# daGloane.net
KiCad netlist of a schematic drawn in EAGLE
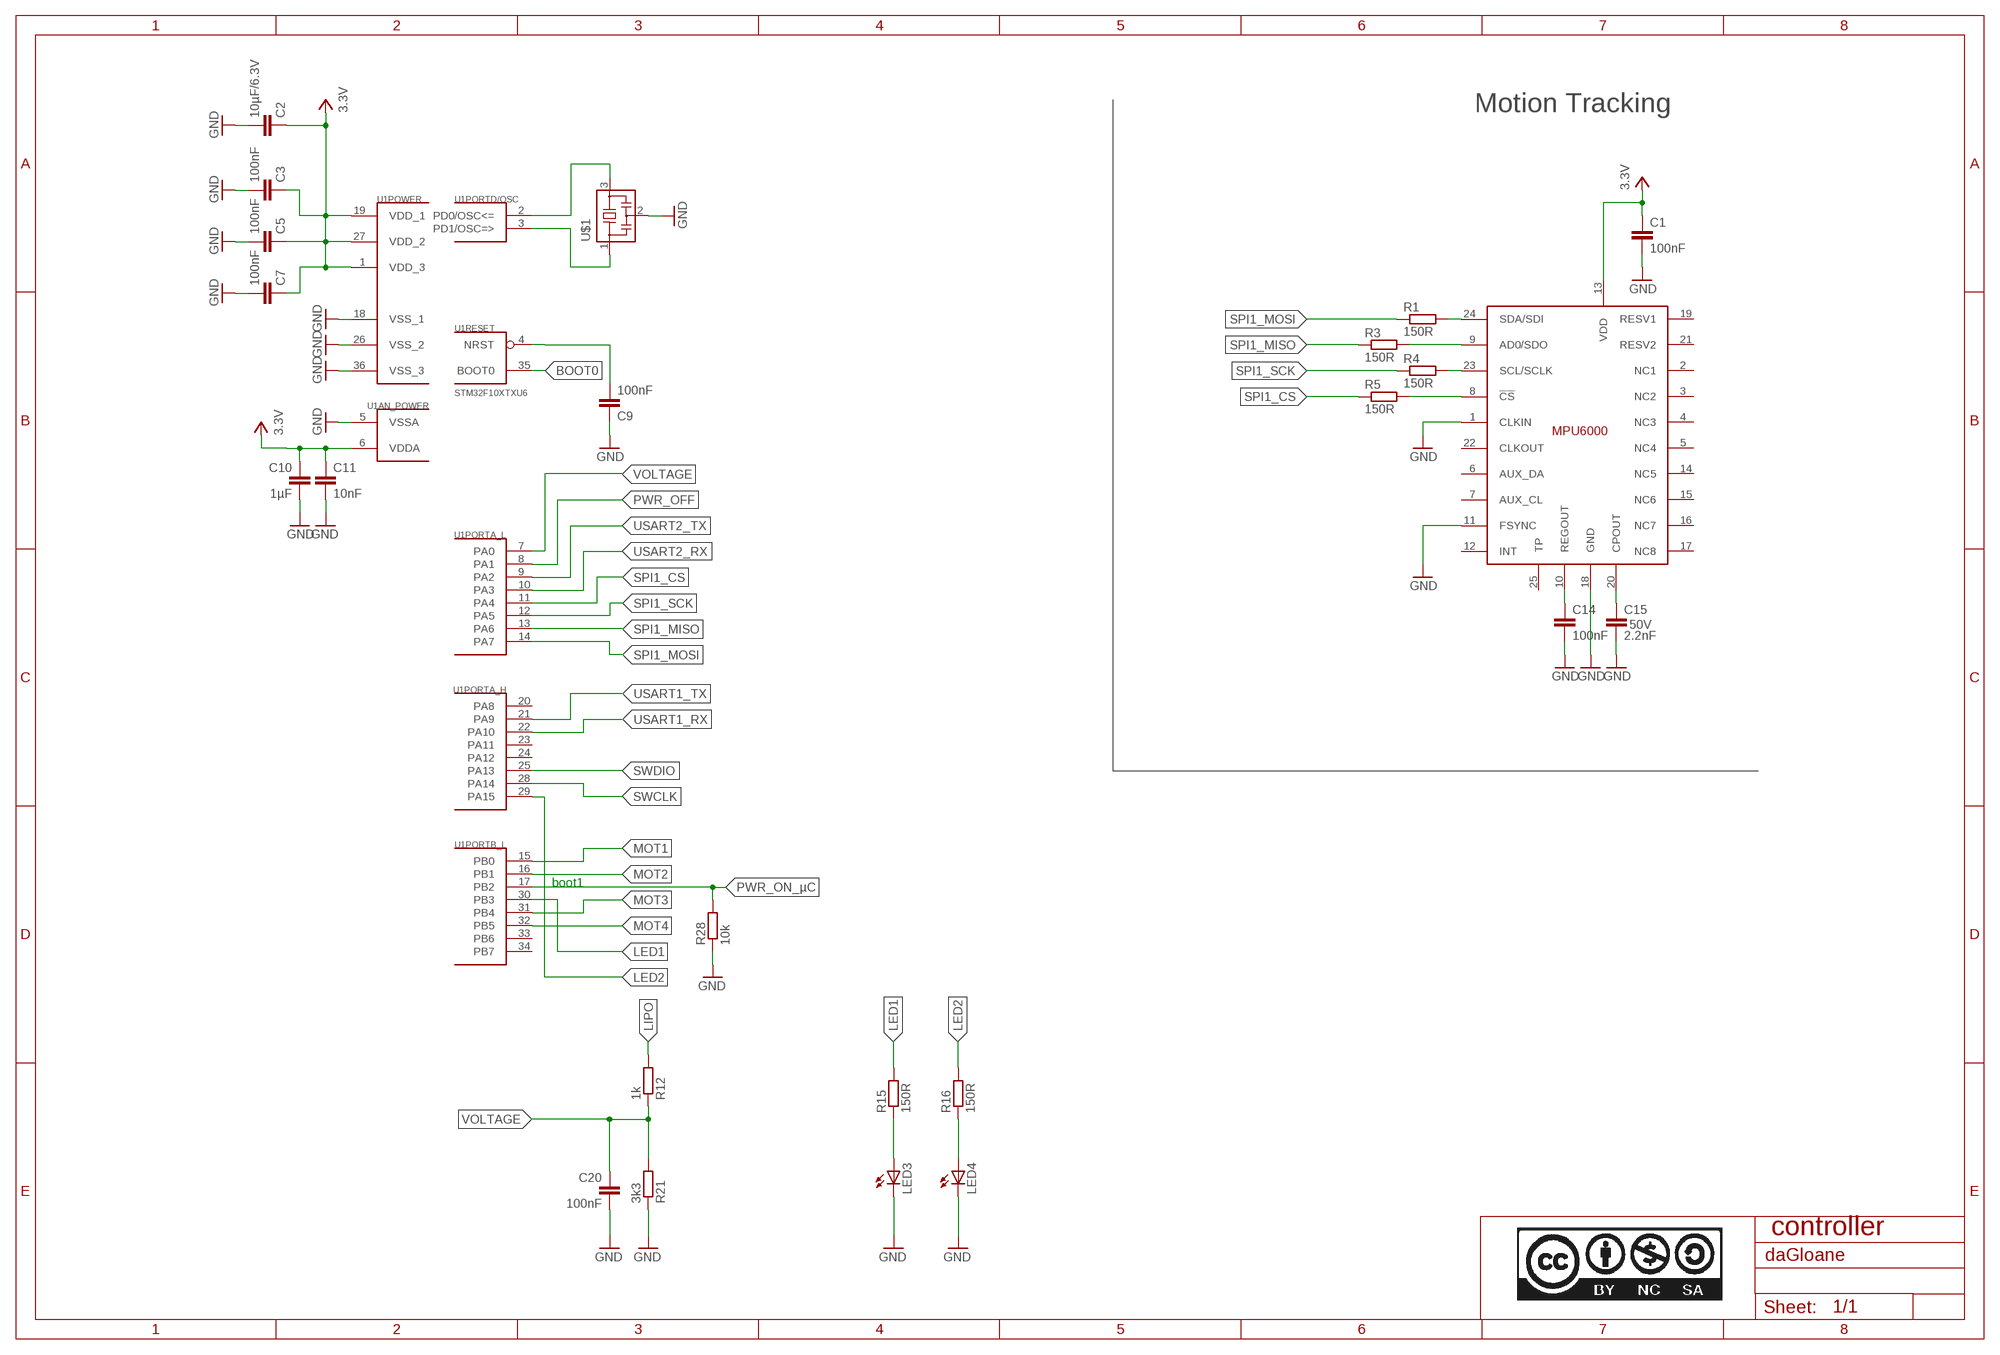
[diagram p0: schematic, sheet 1, part 1 of 3]
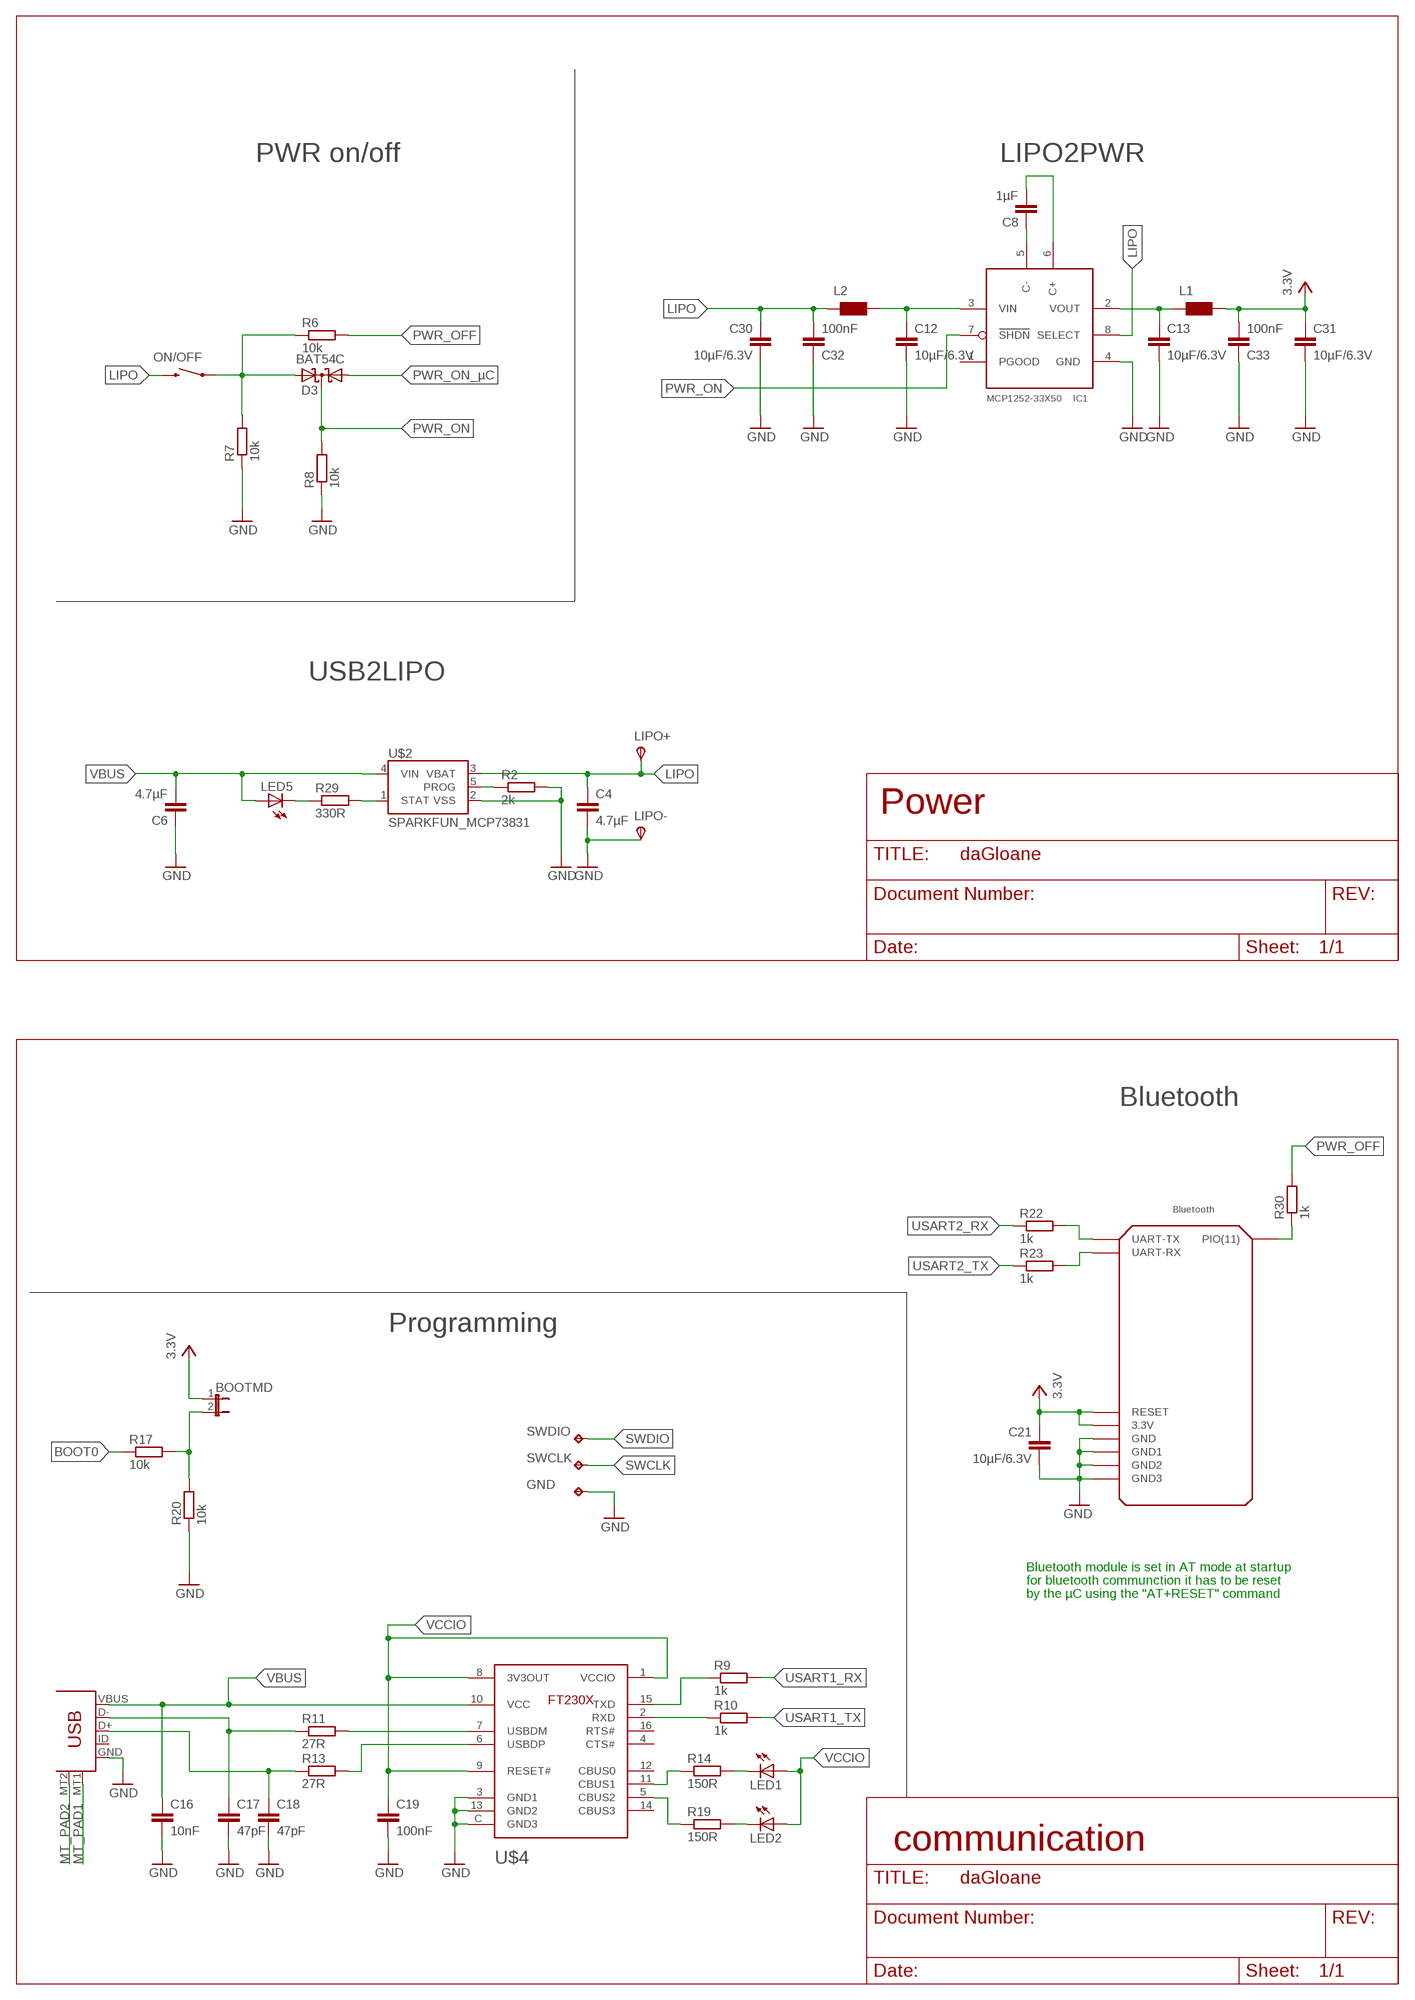
[diagram p1: schematic, sheet 1, part 2 of 3]
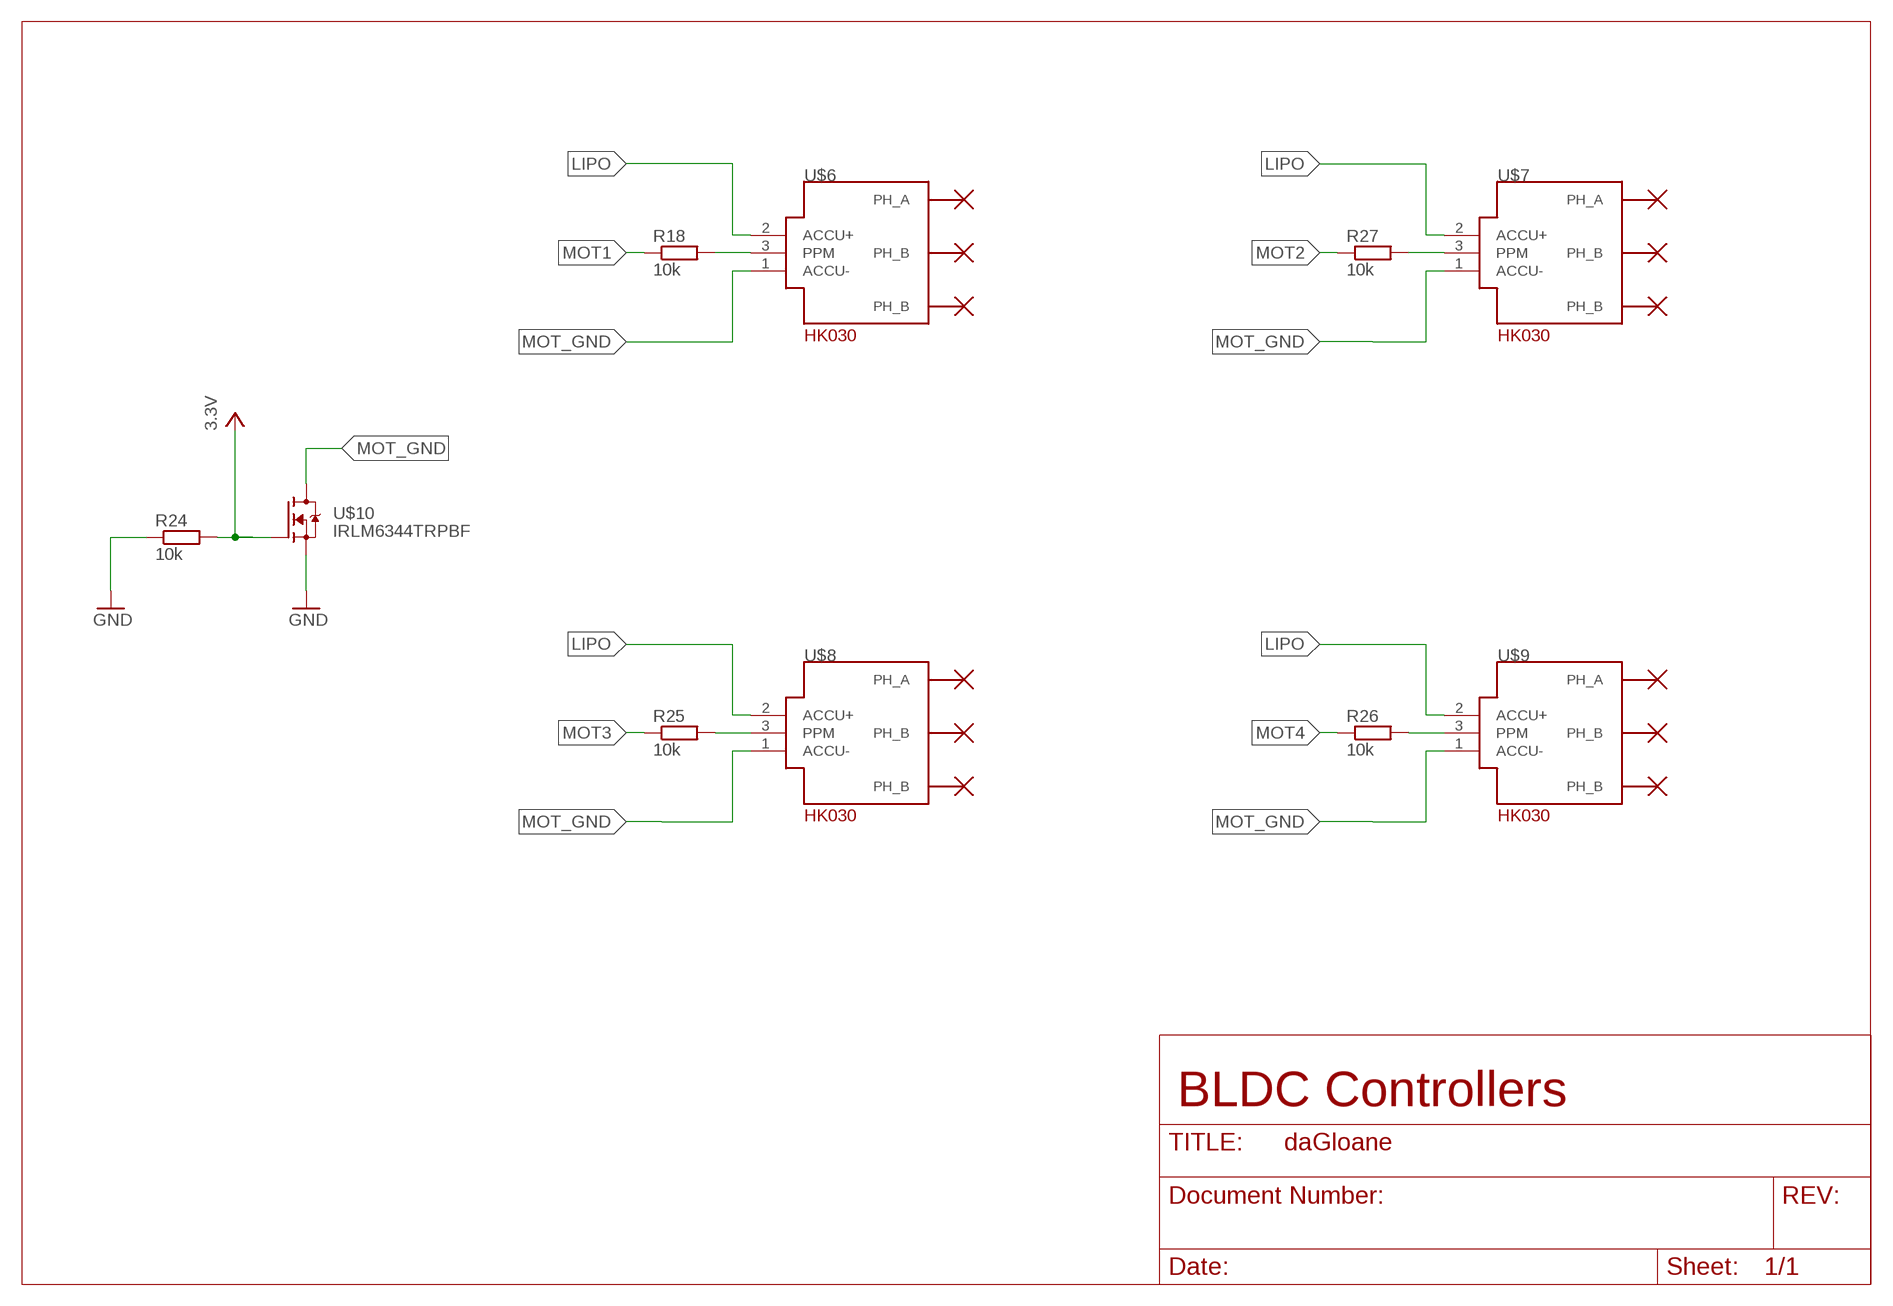
[diagram p2: schematic, sheet 1, part 3 of 3]

(export (version "E")
  (design (tool "Eeschema 10.0.6"))
  (components
    (comp (ref "BOOTMD")
      (value "JUMPER-2")
      (footprint "eagle-import:1X02_50MIL")
      (libsource (lib "eagle-import") (part "JUMPER-2"))
    )
    (comp (ref "C1")
      (value "100nF")
      (footprint "eagle-import:C0603")
      (libsource (lib "eagle-import") (part "C-EUC0603"))
    )
    (comp (ref "C2")
      (value "10µF/6.3V")
      (footprint "eagle-import:C0805")
      (libsource (lib "eagle-import") (part "C-EUC0805"))
    )
    (comp (ref "C3")
      (value "100nF")
      (footprint "eagle-import:C0603")
      (libsource (lib "eagle-import") (part "C-EUC0603"))
    )
    (comp (ref "C4")
      (value "4.7µF")
      (footprint "eagle-import:C0603")
      (libsource (lib "eagle-import") (part "C-EUC0603"))
    )
    (comp (ref "C5")
      (value "100nF")
      (footprint "eagle-import:C0603")
      (libsource (lib "eagle-import") (part "C-EUC0603"))
    )
    (comp (ref "C6")
      (value "4.7µF")
      (footprint "eagle-import:C0603")
      (libsource (lib "eagle-import") (part "C-EUC0603"))
    )
    (comp (ref "C7")
      (value "100nF")
      (footprint "eagle-import:C0603")
      (libsource (lib "eagle-import") (part "C-EUC0603"))
    )
    (comp (ref "C8")
      (value "1µF")
      (footprint "eagle-import:C0603")
      (libsource (lib "eagle-import") (part "C-EUC0603"))
    )
    (comp (ref "C9")
      (value "100nF")
      (footprint "eagle-import:C0603")
      (libsource (lib "eagle-import") (part "C-EUC0603"))
    )
    (comp (ref "C10")
      (value "1µF")
      (footprint "eagle-import:C0603")
      (libsource (lib "eagle-import") (part "C-EUC0603"))
    )
    (comp (ref "C11")
      (value "10nF")
      (footprint "eagle-import:C0603")
      (libsource (lib "eagle-import") (part "C-EUC0603"))
    )
    (comp (ref "C12")
      (value "10µF/6.3V")
      (footprint "eagle-import:C0805")
      (libsource (lib "eagle-import") (part "C-EUC0805"))
    )
    (comp (ref "C13")
      (value "10µF/6.3V")
      (footprint "eagle-import:C0805")
      (libsource (lib "eagle-import") (part "C-EUC0805"))
    )
    (comp (ref "C14")
      (value "100nF")
      (footprint "eagle-import:C0603")
      (libsource (lib "eagle-import") (part "C-EUC0603"))
    )
    (comp (ref "C15")
      (value "2.2nF")
      (footprint "eagle-import:C0603")
      (fields (field (name "VOLTAGE") "50V"))
      (libsource (lib "eagle-import") (part "C-EUC0603"))
    )
    (comp (ref "C16")
      (value "10nF")
      (footprint "eagle-import:C0603")
      (libsource (lib "eagle-import") (part "C-EUC0603"))
    )
    (comp (ref "C17")
      (value "47pF")
      (footprint "eagle-import:C0603")
      (libsource (lib "eagle-import") (part "C-EUC0603"))
    )
    (comp (ref "C18")
      (value "47pF")
      (footprint "eagle-import:C0603")
      (libsource (lib "eagle-import") (part "C-EUC0603"))
    )
    (comp (ref "C19")
      (value "100nF")
      (footprint "eagle-import:C0603")
      (libsource (lib "eagle-import") (part "C-EUC0603"))
    )
    (comp (ref "C20")
      (value "100nF")
      (footprint "eagle-import:C0603")
      (libsource (lib "eagle-import") (part "C-EUC0603"))
    )
    (comp (ref "C21")
      (value "10µF/6.3V")
      (footprint "eagle-import:C0805")
      (libsource (lib "eagle-import") (part "C-EUC0805"))
    )
    (comp (ref "C30")
      (value "10µF/6.3V")
      (footprint "eagle-import:C0805")
      (libsource (lib "eagle-import") (part "C-EUC0805"))
    )
    (comp (ref "C31")
      (value "10µF/6.3V")
      (footprint "eagle-import:C0805")
      (libsource (lib "eagle-import") (part "C-EUC0805"))
    )
    (comp (ref "C32")
      (value "100nF")
      (footprint "eagle-import:C0603")
      (libsource (lib "eagle-import") (part "C-EUC0603"))
    )
    (comp (ref "C33")
      (value "100nF")
      (footprint "eagle-import:C0603")
      (libsource (lib "eagle-import") (part "C-EUC0603"))
    )
    (comp (ref "D3")
      (value "BAT54C")
      (footprint "eagle-import:SOT23")
      (libsource (lib "eagle-import") (part "BAT54C"))
    )
    (comp (ref "GND")
      (value "TESTPAD_TPB1,27")
      (footprint "eagle-import:TESTPAD_B1,27")
      (libsource (lib "eagle-import") (part "TESTPAD_TPB1,27"))
    )
    (comp (ref "IC1")
      (value "MCP1252-33X50")
      (footprint "eagle-import:MSOP8")
      (libsource (lib "eagle-import") (part "MCP1252-33X50"))
    )
    (comp (ref "L1")
      (value "WUERTH-ELEKTRONIK_WE-KI_0805_B")
      (footprint "eagle-import:WUERTH-ELEKTRONIK_WE-KI_0805_B")
      (libsource (lib "eagle-import") (part "WUERTH-ELEKTRONIK_WE-KI_0805_B"))
    )
    (comp (ref "L2")
      (value "WUERTH-ELEKTRONIK_WE-KI_0805_B")
      (footprint "eagle-import:WUERTH-ELEKTRONIK_WE-KI_0805_B")
      (libsource (lib "eagle-import") (part "WUERTH-ELEKTRONIK_WE-KI_0805_B"))
    )
    (comp (ref "LED1")
      (value "LEDCHIPLED_0603")
      (footprint "eagle-import:CHIPLED_0603")
      (libsource (lib "eagle-import") (part "LEDCHIPLED_0603"))
    )
    (comp (ref "LED2")
      (value "LEDCHIPLED_0603")
      (footprint "eagle-import:CHIPLED_0603")
      (libsource (lib "eagle-import") (part "LEDCHIPLED_0603"))
    )
    (comp (ref "LED3")
      (value "LEDCHIPLED_0603")
      (footprint "eagle-import:CHIPLED_0603")
      (libsource (lib "eagle-import") (part "LEDCHIPLED_0603"))
    )
    (comp (ref "LED4")
      (value "LEDCHIPLED_0603")
      (footprint "eagle-import:CHIPLED_0603")
      (libsource (lib "eagle-import") (part "LEDCHIPLED_0603"))
    )
    (comp (ref "LED5")
      (value "LEDCHIPLED_0603")
      (footprint "eagle-import:CHIPLED_0603")
      (libsource (lib "eagle-import") (part "LEDCHIPLED_0603"))
    )
    (comp (ref "LIPO+")
      (value "TPSPAD1-13")
      (footprint "eagle-import:P1-13")
      (libsource (lib "eagle-import") (part "TPSPAD1-13"))
    )
    (comp (ref "LIPO-")
      (value "TPSPAD1-13")
      (footprint "eagle-import:P1-13")
      (libsource (lib "eagle-import") (part "TPSPAD1-13"))
    )
    (comp (ref "ON/OFF")
      (value "SWITCH-MOMENTARY-2SMD")
      (footprint "eagle-import:TACTILE_SWITCH_SMD")
      (libsource (lib "eagle-import") (part "SWITCH-MOMENTARY-2SMD"))
    )
    (comp (ref "R1")
      (value "150R")
      (footprint "eagle-import:R0603")
      (libsource (lib "eagle-import") (part "R-EU_R0603"))
    )
    (comp (ref "R2")
      (value "2k")
      (footprint "eagle-import:R0603")
      (libsource (lib "eagle-import") (part "R-EU_R0603"))
    )
    (comp (ref "R3")
      (value "150R")
      (footprint "eagle-import:R0603")
      (libsource (lib "eagle-import") (part "R-EU_R0603"))
    )
    (comp (ref "R4")
      (value "150R")
      (footprint "eagle-import:R0603")
      (libsource (lib "eagle-import") (part "R-EU_R0603"))
    )
    (comp (ref "R5")
      (value "150R")
      (footprint "eagle-import:R0603")
      (libsource (lib "eagle-import") (part "R-EU_R0603"))
    )
    (comp (ref "R6")
      (value "10k")
      (footprint "eagle-import:R0603")
      (libsource (lib "eagle-import") (part "R-EU_R0603"))
    )
    (comp (ref "R7")
      (value "10k")
      (footprint "eagle-import:R0603")
      (libsource (lib "eagle-import") (part "R-EU_R0603"))
    )
    (comp (ref "R8")
      (value "10k")
      (footprint "eagle-import:R0603")
      (libsource (lib "eagle-import") (part "R-EU_R0603"))
    )
    (comp (ref "R9")
      (value "1k")
      (footprint "eagle-import:R0603")
      (libsource (lib "eagle-import") (part "R-EU_R0603"))
    )
    (comp (ref "R10")
      (value "1k")
      (footprint "eagle-import:R0603")
      (libsource (lib "eagle-import") (part "R-EU_R0603"))
    )
    (comp (ref "R11")
      (value "27R")
      (footprint "eagle-import:R0603")
      (libsource (lib "eagle-import") (part "R-EU_R0603"))
    )
    (comp (ref "R12")
      (value "1k")
      (footprint "eagle-import:R0603")
      (libsource (lib "eagle-import") (part "R-EU_R0603"))
    )
    (comp (ref "R13")
      (value "27R")
      (footprint "eagle-import:R0603")
      (libsource (lib "eagle-import") (part "R-EU_R0603"))
    )
    (comp (ref "R14")
      (value "150R")
      (footprint "eagle-import:R0603")
      (libsource (lib "eagle-import") (part "R-EU_R0603"))
    )
    (comp (ref "R15")
      (value "150R")
      (footprint "eagle-import:R0603")
      (libsource (lib "eagle-import") (part "R-EU_R0603"))
    )
    (comp (ref "R16")
      (value "150R")
      (footprint "eagle-import:R0603")
      (libsource (lib "eagle-import") (part "R-EU_R0603"))
    )
    (comp (ref "R17")
      (value "10k")
      (footprint "eagle-import:R0603")
      (libsource (lib "eagle-import") (part "R-EU_R0603"))
    )
    (comp (ref "R18")
      (value "10k")
      (footprint "eagle-import:R0603")
      (libsource (lib "eagle-import") (part "R-EU_R0603"))
    )
    (comp (ref "R19")
      (value "150R")
      (footprint "eagle-import:R0603")
      (libsource (lib "eagle-import") (part "R-EU_R0603"))
    )
    (comp (ref "R20")
      (value "10k")
      (footprint "eagle-import:R0603")
      (libsource (lib "eagle-import") (part "R-EU_R0603"))
    )
    (comp (ref "R21")
      (value "3k3")
      (footprint "eagle-import:R0603")
      (libsource (lib "eagle-import") (part "R-EU_R0603"))
    )
    (comp (ref "R22")
      (value "1k")
      (footprint "eagle-import:R0603")
      (libsource (lib "eagle-import") (part "R-EU_R0603"))
    )
    (comp (ref "R23")
      (value "1k")
      (footprint "eagle-import:R0603")
      (libsource (lib "eagle-import") (part "R-EU_R0603"))
    )
    (comp (ref "R24")
      (value "10k")
      (footprint "eagle-import:R0603")
      (libsource (lib "eagle-import") (part "R-EU_R0603"))
    )
    (comp (ref "R25")
      (value "10k")
      (footprint "eagle-import:R0603")
      (libsource (lib "eagle-import") (part "R-EU_R0603"))
    )
    (comp (ref "R26")
      (value "10k")
      (footprint "eagle-import:R0603")
      (libsource (lib "eagle-import") (part "R-EU_R0603"))
    )
    (comp (ref "R27")
      (value "10k")
      (footprint "eagle-import:R0603")
      (libsource (lib "eagle-import") (part "R-EU_R0603"))
    )
    (comp (ref "R28")
      (value "10k")
      (footprint "eagle-import:R0603")
      (libsource (lib "eagle-import") (part "R-EU_R0603"))
    )
    (comp (ref "R29")
      (value "330R")
      (footprint "eagle-import:R0603")
      (libsource (lib "eagle-import") (part "R-EU_R0603"))
    )
    (comp (ref "R30")
      (value "1k")
      (footprint "eagle-import:R0603")
      (libsource (lib "eagle-import") (part "R-EU_R0603"))
    )
    (comp (ref "SWCLK")
      (value "TESTPAD_TPB1,27")
      (footprint "eagle-import:TESTPAD_B1,27")
      (libsource (lib "eagle-import") (part "TESTPAD_TPB1,27"))
    )
    (comp (ref "SWDIO")
      (value "TESTPAD_TPB1,27")
      (footprint "eagle-import:TESTPAD_B1,27")
      (libsource (lib "eagle-import") (part "TESTPAD_TPB1,27"))
    )
    (comp (ref "U$1")
      (value "MURATA-FILTER_CSTCE__G")
      (footprint "eagle-import:MURATA-FILTER_CSTCE__G")
      (libsource (lib "eagle-import") (part "MURATA-FILTER_CSTCE__G"))
    )
    (comp (ref "U$2")
      (value "SPARKFUN_MCP73831")
      (footprint "eagle-import:SPARKFUN_SOT23-5")
      (libsource (lib "eagle-import") (part "SPARKFUN_MCP73831"))
    )
    (comp (ref "U$3")
      (value "MPU6000")
      (footprint "eagle-import:MPU6000")
      (libsource (lib "eagle-import") (part "MPU6000"))
    )
    (comp (ref "U$4")
      (value "SERIAL_FT230XQ")
      (footprint "eagle-import:SERIAL_QFN4X4-16")
      (libsource (lib "eagle-import") (part "SERIAL_FT230XQ"))
    )
    (comp (ref "U$5")
      (value "BLUETOOTH_REDUCED")
      (footprint "eagle-import:BLUETOOTH_REDUCED")
      (libsource (lib "eagle-import") (part "BLUETOOTH_REDUCED"))
    )
    (comp (ref "U$6")
      (value "3A_BLDC_CONTROLLER")
      (footprint "eagle-import:3A_BLDC_CONTROLLER")
      (libsource (lib "eagle-import") (part "3A_BLDC_CONTROLLER"))
    )
    (comp (ref "U$7")
      (value "3A_BLDC_CONTROLLER")
      (footprint "eagle-import:3A_BLDC_CONTROLLER")
      (libsource (lib "eagle-import") (part "3A_BLDC_CONTROLLER"))
    )
    (comp (ref "U$8")
      (value "3A_BLDC_CONTROLLER")
      (footprint "eagle-import:3A_BLDC_CONTROLLER")
      (libsource (lib "eagle-import") (part "3A_BLDC_CONTROLLER"))
    )
    (comp (ref "U$9")
      (value "3A_BLDC_CONTROLLER")
      (footprint "eagle-import:3A_BLDC_CONTROLLER")
      (libsource (lib "eagle-import") (part "3A_BLDC_CONTROLLER"))
    )
    (comp (ref "U$10")
      (value "IRLM6344TRPBF")
      (footprint "eagle-import:MICRO3(SOT-23)")
      (libsource (lib "eagle-import") (part "IRLM6344TRPBF"))
    )
    (comp (ref "U1")
      (value "STM32F10XTXU6")
      (footprint "eagle-import:VFQFPN36")
      (libsource (lib "eagle-import") (part "STM32F10XTXU6"))
    )
    (comp (ref "X2")
      (value "USB_MICROB_PLUG_MT")
      (footprint "eagle-import:SPARKFUN-CONNECTORS_USB-MICROB")
      (libsource (lib "eagle-import") (part "USB_MICROB_PLUG_MT"))
    )
  )
  (nets
    (net (code "3") (name "/MT_PAD1") (class "Default")
      (node (ref "X2") (pin "MT1") (pinfunction "MTN1_MT1") (pintype "no_connect"))
    )
    (net (code "4") (name "/MT_PAD2") (class "Default")
      (node (ref "X2") (pin "MT2") (pinfunction "MTN2_MT2") (pintype "no_connect"))
    )
    (net (code "5") (name "3.3V") (class "Default")
      (node (ref "BOOTMD") (pin "1") (pinfunction "1_1") (pintype "passive"))
      (node (ref "C1") (pin "1") (pinfunction "1_1") (pintype "passive"))
      (node (ref "C10") (pin "1") (pinfunction "1_1") (pintype "passive"))
      (node (ref "C11") (pin "1") (pinfunction "1_1") (pintype "passive"))
      (node (ref "C2") (pin "1") (pinfunction "1_1") (pintype "passive"))
      (node (ref "C21") (pin "1") (pinfunction "1_1") (pintype "passive"))
      (node (ref "C3") (pin "1") (pinfunction "1_1") (pintype "passive"))
      (node (ref "C31") (pin "1") (pinfunction "1_1") (pintype "passive"))
      (node (ref "C33") (pin "2") (pinfunction "2_2") (pintype "passive"))
      (node (ref "C5") (pin "1") (pinfunction "1_1") (pintype "passive"))
      (node (ref "C7") (pin "1") (pinfunction "1_1") (pintype "passive"))
      (node (ref "L1") (pin "1") (pinfunction "2_1") (pintype "passive"))
      (node (ref "R24") (pin "2") (pinfunction "2_2") (pintype "passive"))
      (node (ref "U$10") (pin "1") (pinfunction "G_1") (pintype "passive"))
      (node (ref "U$3") (pin "13") (pinfunction "VDD_13") (pintype "power_in"))
      (node (ref "U$5") (pin "P$11") (pinfunction "RESET_P$11") (pintype "input"))
      (node (ref "U$5") (pin "P$12") (pinfunction "3.3V_P$12") (pintype "power_in"))
      (node (ref "U1") (pin "1") (pinfunction "VDD_3_1") (pintype "power_in"))
      (node (ref "U1") (pin "19") (pinfunction "VDD_1_19") (pintype "power_in"))
      (node (ref "U1") (pin "27") (pinfunction "VDD_2_27") (pintype "power_in"))
      (node (ref "U1") (pin "6") (pinfunction "VDDA_6") (pintype "power_in"))
    )
    (net (code "6") (name "BOOT0") (class "Default")
      (node (ref "R17") (pin "1") (pinfunction "1_1") (pintype "passive"))
      (node (ref "U1") (pin "35") (pinfunction "BOOT0_35") (pintype "input"))
    )
    (net (code "7") (name "GND") (class "Default")
      (node (ref "C1") (pin "2") (pinfunction "2_2") (pintype "passive"))
      (node (ref "C10") (pin "2") (pinfunction "2_2") (pintype "passive"))
      (node (ref "C11") (pin "2") (pinfunction "2_2") (pintype "passive"))
      (node (ref "C12") (pin "2") (pinfunction "2_2") (pintype "passive"))
      (node (ref "C13") (pin "2") (pinfunction "2_2") (pintype "passive"))
      (node (ref "C14") (pin "2") (pinfunction "2_2") (pintype "passive"))
      (node (ref "C15") (pin "2") (pinfunction "2_2") (pintype "passive"))
      (node (ref "C16") (pin "2") (pinfunction "2_2") (pintype "passive"))
      (node (ref "C17") (pin "2") (pinfunction "2_2") (pintype "passive"))
      (node (ref "C18") (pin "2") (pinfunction "2_2") (pintype "passive"))
      (node (ref "C19") (pin "2") (pinfunction "2_2") (pintype "passive"))
      (node (ref "C2") (pin "2") (pinfunction "2_2") (pintype "passive"))
      (node (ref "C20") (pin "2") (pinfunction "2_2") (pintype "passive"))
      (node (ref "C21") (pin "2") (pinfunction "2_2") (pintype "passive"))
      (node (ref "C3") (pin "2") (pinfunction "2_2") (pintype "passive"))
      (node (ref "C30") (pin "2") (pinfunction "2_2") (pintype "passive"))
      (node (ref "C31") (pin "2") (pinfunction "2_2") (pintype "passive"))
      (node (ref "C32") (pin "1") (pinfunction "1_1") (pintype "passive"))
      (node (ref "C33") (pin "1") (pinfunction "1_1") (pintype "passive"))
      (node (ref "C4") (pin "2") (pinfunction "2_2") (pintype "passive"))
      (node (ref "C5") (pin "2") (pinfunction "2_2") (pintype "passive"))
      (node (ref "C6") (pin "1") (pinfunction "1_1") (pintype "passive"))
      (node (ref "C7") (pin "2") (pinfunction "2_2") (pintype "passive"))
      (node (ref "C9") (pin "1") (pinfunction "1_1") (pintype "passive"))
      (node (ref "GND") (pin "PP") (pinfunction "TP_PP") (pintype "input"))
      (node (ref "IC1") (pin "4") (pinfunction "GND_4") (pintype "power_in"))
      (node (ref "LED3") (pin "C") (pinfunction "C_C") (pintype "passive"))
      (node (ref "LED4") (pin "C") (pinfunction "C_C") (pintype "passive"))
      (node (ref "LIPO-") (pin "TP") (pinfunction "PP_TP") (pintype "input"))
      (node (ref "R2") (pin "2") (pinfunction "2_2") (pintype "passive"))
      (node (ref "R20") (pin "1") (pinfunction "1_1") (pintype "passive"))
      (node (ref "R21") (pin "1") (pinfunction "1_1") (pintype "passive"))
      (node (ref "R24") (pin "1") (pinfunction "1_1") (pintype "passive"))
      (node (ref "R28") (pin "1") (pinfunction "1_1") (pintype "passive"))
      (node (ref "R7") (pin "1") (pinfunction "1_1") (pintype "passive"))
      (node (ref "R8") (pin "1") (pinfunction "1_1") (pintype "passive"))
      (node (ref "U$1") (pin "2") (pinfunction "2_2") (pintype "passive"))
      (node (ref "U$10") (pin "2") (pinfunction "S_2") (pintype "passive"))
      (node (ref "U$2") (pin "2") (pinfunction "VSS_2") (pintype "power_in"))
      (node (ref "U$3") (pin "1") (pinfunction "CLKIN_1") (pintype "input"))
      (node (ref "U$3") (pin "11") (pinfunction "FSYNC_11") (pintype "input"))
      (node (ref "U$3") (pin "18") (pinfunction "GND_18") (pintype "power_in"))
      (node (ref "U$4") (pin "13") (pinfunction "GND2_13") (pintype "power_in"))
      (node (ref "U$4") (pin "3") (pinfunction "GND1_3") (pintype "power_in"))
      (node (ref "U$4") (pin "C") (pinfunction "GND3_C") (pintype "power_in"))
      (node (ref "U$5") (pin "P$13") (pinfunction "GND_P$13") (pintype "power_in"))
      (node (ref "U$5") (pin "P$14") (pinfunction "GND1_P$14") (pintype "power_in"))
      (node (ref "U$5") (pin "P$21") (pinfunction "GND2_P$21") (pintype "power_in"))
      (node (ref "U$5") (pin "P$22") (pinfunction "GND3_P$22") (pintype "power_in"))
      (node (ref "U1") (pin "18") (pinfunction "VSS_1_18") (pintype "power_in"))
      (node (ref "U1") (pin "26") (pinfunction "VSS_2_26") (pintype "power_in"))
      (node (ref "U1") (pin "36") (pinfunction "VSS_3_36") (pintype "power_in"))
      (node (ref "U1") (pin "5") (pinfunction "VSSA_5") (pintype "power_in"))
      (node (ref "X2") (pin "GND") (pinfunction "GND_GND") (pintype "bidirectional"))
    )
    (net (code "8") (name "LED1") (class "Default")
      (node (ref "R15") (pin "2") (pinfunction "2_2") (pintype "passive"))
      (node (ref "U1") (pin "30") (pinfunction "PB3_30") (pintype "bidirectional"))
    )
    (net (code "9") (name "LED2") (class "Default")
      (node (ref "R16") (pin "2") (pinfunction "2_2") (pintype "passive"))
      (node (ref "U1") (pin "29") (pinfunction "PA15_29") (pintype "bidirectional"))
    )
    (net (code "10") (name "LIPO") (class "Default")
      (node (ref "C30") (pin "1") (pinfunction "1_1") (pintype "passive"))
      (node (ref "C32") (pin "2") (pinfunction "2_2") (pintype "passive"))
      (node (ref "C4") (pin "1") (pinfunction "1_1") (pintype "passive"))
      (node (ref "IC1") (pin "8") (pinfunction "SELECT_8") (pintype "input"))
      (node (ref "L2") (pin "2") (pinfunction "1_2") (pintype "passive"))
      (node (ref "LIPO+") (pin "TP") (pinfunction "PP_TP") (pintype "input"))
      (node (ref "ON/OFF") (pin "3") (pinfunction "2_3") (pintype "passive"))
      (node (ref "R12") (pin "2") (pinfunction "2_2") (pintype "passive"))
      (node (ref "U$2") (pin "3") (pinfunction "VBAT_3") (pintype "power_in"))
      (node (ref "U$6") (pin "2") (pinfunction "ACCU+_2") (pintype "power_in"))
      (node (ref "U$7") (pin "2") (pinfunction "ACCU+_2") (pintype "power_in"))
      (node (ref "U$8") (pin "2") (pinfunction "ACCU+_2") (pintype "power_in"))
      (node (ref "U$9") (pin "2") (pinfunction "ACCU+_2") (pintype "power_in"))
    )
    (net (code "11") (name "MOT1") (class "Default")
      (node (ref "R18") (pin "1") (pinfunction "1_1") (pintype "passive"))
      (node (ref "U1") (pin "15") (pinfunction "PB0_15") (pintype "bidirectional"))
    )
    (net (code "12") (name "MOT2") (class "Default")
      (node (ref "R27") (pin "1") (pinfunction "1_1") (pintype "passive"))
      (node (ref "U1") (pin "16") (pinfunction "PB1_16") (pintype "bidirectional"))
    )
    (net (code "13") (name "MOT3") (class "Default")
      (node (ref "R25") (pin "1") (pinfunction "1_1") (pintype "passive"))
      (node (ref "U1") (pin "31") (pinfunction "PB4_31") (pintype "bidirectional"))
    )
    (net (code "14") (name "MOT4") (class "Default")
      (node (ref "R26") (pin "1") (pinfunction "1_1") (pintype "passive"))
      (node (ref "U1") (pin "32") (pinfunction "PB5_32") (pintype "bidirectional"))
    )
    (net (code "15") (name "MOT_GND") (class "Default")
      (node (ref "U$10") (pin "3") (pinfunction "D_3") (pintype "passive"))
      (node (ref "U$6") (pin "1") (pinfunction "ACCU-_1") (pintype "power_in"))
      (node (ref "U$7") (pin "1") (pinfunction "ACCU-_1") (pintype "power_in"))
      (node (ref "U$8") (pin "1") (pinfunction "ACCU-_1") (pintype "power_in"))
      (node (ref "U$9") (pin "1") (pinfunction "ACCU-_1") (pintype "power_in"))
    )
    (net (code "16") (name "Net-(BOOTMD-Pad2)") (class "Default")
      (node (ref "BOOTMD") (pin "2") (pinfunction "2_2") (pintype "passive"))
      (node (ref "R17") (pin "2") (pinfunction "2_2") (pintype "passive"))
      (node (ref "R20") (pin "2") (pinfunction "2_2") (pintype "passive"))
    )
    (net (code "17") (name "Net-(C17-Pad1)") (class "Default")
      (node (ref "C17") (pin "1") (pinfunction "1_1") (pintype "passive"))
      (node (ref "R11") (pin "1") (pinfunction "1_1") (pintype "passive"))
      (node (ref "X2") (pin "D-") (pinfunction "D-_D-") (pintype "bidirectional"))
    )
    (net (code "18") (name "Net-(C18-Pad1)") (class "Default")
      (node (ref "C18") (pin "1") (pinfunction "1_1") (pintype "passive"))
      (node (ref "R13") (pin "1") (pinfunction "1_1") (pintype "passive"))
      (node (ref "X2") (pin "D+") (pinfunction "D+_D+") (pintype "bidirectional"))
    )
    (net (code "19") (name "Net-(D3-A2)") (class "Default")
      (node (ref "D3") (pin "2") (pinfunction "A2_2") (pintype "passive"))
      (node (ref "ON/OFF") (pin "1") (pinfunction "1_1") (pintype "passive"))
      (node (ref "R6") (pin "1") (pinfunction "1_1") (pintype "passive"))
      (node (ref "R7") (pin "2") (pinfunction "2_2") (pintype "passive"))
    )
    (net (code "20") (name "Net-(IC1-C+)") (class "Default")
      (node (ref "C8") (pin "2") (pinfunction "2_2") (pintype "passive"))
      (node (ref "IC1") (pin "6") (pinfunction "C+_6") (pintype "passive"))
    )
    (net (code "21") (name "Net-(IC1-C-)") (class "Default")
      (node (ref "C8") (pin "1") (pinfunction "1_1") (pintype "passive"))
      (node (ref "IC1") (pin "5") (pinfunction "C-_5") (pintype "passive"))
    )
    (net (code "22") (name "Net-(IC1-VIN)") (class "Default")
      (node (ref "C12") (pin "1") (pinfunction "1_1") (pintype "passive"))
      (node (ref "IC1") (pin "3") (pinfunction "VIN_3") (pintype "power_in"))
      (node (ref "L2") (pin "1") (pinfunction "2_1") (pintype "passive"))
    )
    (net (code "23") (name "Net-(IC1-VOUT)") (class "Default")
      (node (ref "C13") (pin "1") (pinfunction "1_1") (pintype "passive"))
      (node (ref "IC1") (pin "2") (pinfunction "VOUT_2") (pintype "output"))
      (node (ref "L1") (pin "2") (pinfunction "1_2") (pintype "passive"))
    )
    (net (code "24") (name "Net-(LED1-PadC)") (class "Default")
      (node (ref "LED1") (pin "C") (pinfunction "C_C") (pintype "passive"))
      (node (ref "R14") (pin "2") (pinfunction "2_2") (pintype "passive"))
    )
    (net (code "25") (name "Net-(LED2-PadC)") (class "Default")
      (node (ref "LED2") (pin "C") (pinfunction "C_C") (pintype "passive"))
      (node (ref "R19") (pin "2") (pinfunction "2_2") (pintype "passive"))
    )
    (net (code "26") (name "Net-(LED3-PadA)") (class "Default")
      (node (ref "LED3") (pin "A") (pinfunction "A_A") (pintype "passive"))
      (node (ref "R15") (pin "1") (pinfunction "1_1") (pintype "passive"))
    )
    (net (code "27") (name "Net-(LED4-PadA)") (class "Default")
      (node (ref "LED4") (pin "A") (pinfunction "A_A") (pintype "passive"))
      (node (ref "R16") (pin "1") (pinfunction "1_1") (pintype "passive"))
    )
    (net (code "28") (name "Net-(LED5-PadC)") (class "Default")
      (node (ref "LED5") (pin "C") (pinfunction "C_C") (pintype "passive"))
      (node (ref "R29") (pin "1") (pinfunction "1_1") (pintype "passive"))
    )
    (net (code "29") (name "Net-(U$2-PROG)") (class "Default")
      (node (ref "R2") (pin "1") (pinfunction "1_1") (pintype "passive"))
      (node (ref "U$2") (pin "5") (pinfunction "PROG_5") (pintype "input"))
    )
    (net (code "30") (name "Net-(U$2-STAT)") (class "Default")
      (node (ref "R29") (pin "2") (pinfunction "2_2") (pintype "passive"))
      (node (ref "U$2") (pin "1") (pinfunction "STAT_1") (pintype "output"))
    )
    (net (code "31") (name "Net-(U$3-AD0{slash}SDO)") (class "Default")
      (node (ref "R3") (pin "2") (pinfunction "2_2") (pintype "passive"))
      (node (ref "U$3") (pin "9") (pinfunction "AD0/SDO_9") (pintype "output"))
    )
    (net (code "32") (name "Net-(U$3-CPOUT)") (class "Default")
      (node (ref "C15") (pin "1") (pinfunction "1_1") (pintype "passive"))
      (node (ref "U$3") (pin "20") (pinfunction "CPOUT_20") (pintype "bidirectional"))
    )
    (net (code "33") (name "Net-(U$3-REGOUT)") (class "Default")
      (node (ref "C14") (pin "1") (pinfunction "1_1") (pintype "passive"))
      (node (ref "U$3") (pin "10") (pinfunction "REGOUT_10") (pintype "bidirectional"))
    )
    (net (code "34") (name "Net-(U$3-SCL{slash}SCLK)") (class "Default")
      (node (ref "R4") (pin "2") (pinfunction "2_2") (pintype "passive"))
      (node (ref "U$3") (pin "23") (pinfunction "SCL/SCLK_23") (pintype "input"))
    )
    (net (code "35") (name "Net-(U$3-SDA{slash}SDI)") (class "Default")
      (node (ref "R1") (pin "2") (pinfunction "2_2") (pintype "passive"))
      (node (ref "U$3") (pin "24") (pinfunction "SDA/SDI_24") (pintype "input"))
    )
    (net (code "36") (name "Net-(U$3-~{CS})") (class "Default")
      (node (ref "R5") (pin "2") (pinfunction "2_2") (pintype "passive"))
      (node (ref "U$3") (pin "8") (pinfunction "~{CS}_8") (pintype "input"))
    )
    (net (code "37") (name "Net-(U$4-CBUS1)") (class "Default")
      (node (ref "R14") (pin "1") (pinfunction "1_1") (pintype "passive"))
      (node (ref "U$4") (pin "11") (pinfunction "CBUS1_11") (pintype "bidirectional"))
    )
    (net (code "38") (name "Net-(U$4-CBUS2)") (class "Default")
      (node (ref "R19") (pin "1") (pinfunction "1_1") (pintype "passive"))
      (node (ref "U$4") (pin "5") (pinfunction "CBUS2_5") (pintype "bidirectional"))
    )
    (net (code "39") (name "Net-(U$4-RXD)") (class "Default")
      (node (ref "R10") (pin "1") (pinfunction "1_1") (pintype "passive"))
      (node (ref "U$4") (pin "2") (pinfunction "RXD_2") (pintype "input"))
    )
    (net (code "40") (name "Net-(U$4-TXD)") (class "Default")
      (node (ref "R9") (pin "1") (pinfunction "1_1") (pintype "passive"))
      (node (ref "U$4") (pin "15") (pinfunction "TXD_15") (pintype "output"))
    )
    (net (code "41") (name "Net-(U$4-USBDM)") (class "Default")
      (node (ref "R11") (pin "2") (pinfunction "2_2") (pintype "passive"))
      (node (ref "U$4") (pin "7") (pinfunction "USBDM_7") (pintype "bidirectional"))
    )
    (net (code "42") (name "Net-(U$4-USBDP)") (class "Default")
      (node (ref "R13") (pin "2") (pinfunction "2_2") (pintype "passive"))
      (node (ref "U$4") (pin "6") (pinfunction "USBDP_6") (pintype "bidirectional"))
    )
    (net (code "43") (name "Net-(U$5-PIO(11))") (class "Default")
      (node (ref "R30") (pin "1") (pinfunction "1_1") (pintype "passive"))
      (node (ref "U$5") (pin "P$34") (pinfunction "PIO(11)_P$34") (pintype "bidirectional"))
    )
    (net (code "44") (name "Net-(U$5-UART-RX)") (class "Default")
      (node (ref "R23") (pin "2") (pinfunction "2_2") (pintype "passive"))
      (node (ref "U$5") (pin "P$2") (pinfunction "UART-RX_P$2") (pintype "input"))
    )
    (net (code "45") (name "Net-(U$5-UART-TX)") (class "Default")
      (node (ref "R22") (pin "2") (pinfunction "2_2") (pintype "passive"))
      (node (ref "U$5") (pin "P$1") (pinfunction "UART-TX_P$1") (pintype "output"))
    )
    (net (code "46") (name "Net-(U$6-PPM)") (class "Default")
      (node (ref "R18") (pin "2") (pinfunction "2_2") (pintype "passive"))
      (node (ref "U$6") (pin "3") (pinfunction "PPM_3") (pintype "input"))
    )
    (net (code "47") (name "Net-(U$7-PPM)") (class "Default")
      (node (ref "R27") (pin "2") (pinfunction "2_2") (pintype "passive"))
      (node (ref "U$7") (pin "3") (pinfunction "PPM_3") (pintype "input"))
    )
    (net (code "48") (name "Net-(U$8-PPM)") (class "Default")
      (node (ref "R25") (pin "2") (pinfunction "2_2") (pintype "passive"))
      (node (ref "U$8") (pin "3") (pinfunction "PPM_3") (pintype "input"))
    )
    (net (code "49") (name "Net-(U$9-PPM)") (class "Default")
      (node (ref "R26") (pin "2") (pinfunction "2_2") (pintype "passive"))
      (node (ref "U$9") (pin "3") (pinfunction "PPM_3") (pintype "input"))
    )
    (net (code "50") (name "Net-(U1E-PD0{slash}OSC<=)") (class "Default")
      (node (ref "U$1") (pin "3") (pinfunction "3_3") (pintype "passive"))
      (node (ref "U1") (pin "2") (pinfunction "PD0/OSC<=_2") (pintype "bidirectional"))
    )
    (net (code "51") (name "Net-(U1E-PD1{slash}OSC=>)") (class "Default")
      (node (ref "U$1") (pin "1") (pinfunction "1_1") (pintype "passive"))
      (node (ref "U1") (pin "3") (pinfunction "PD1/OSC=>_3") (pintype "bidirectional"))
    )
    (net (code "52") (name "Net-(U1G-NRST)") (class "Default")
      (node (ref "C9") (pin "2") (pinfunction "2_2") (pintype "passive"))
      (node (ref "U1") (pin "4") (pinfunction "NRST_4") (pintype "input"))
    )
    (net (code "53") (name "PWR_OFF") (class "Default")
      (node (ref "R30") (pin "2") (pinfunction "2_2") (pintype "passive"))
      (node (ref "R6") (pin "2") (pinfunction "2_2") (pintype "passive"))
      (node (ref "U1") (pin "8") (pinfunction "PA1_8") (pintype "bidirectional"))
    )
    (net (code "54") (name "PWR_ON") (class "Default")
      (node (ref "D3") (pin "3") (pinfunction "CC_3") (pintype "passive"))
      (node (ref "IC1") (pin "7") (pinfunction "SHDN_7") (pintype "input"))
      (node (ref "R8") (pin "2") (pinfunction "2_2") (pintype "passive"))
    )
    (net (code "55") (name "PWR_ON_µC") (class "Default")
      (node (ref "D3") (pin "1") (pinfunction "A1_1") (pintype "passive"))
      (node (ref "R28") (pin "2") (pinfunction "2_2") (pintype "passive"))
      (node (ref "U1") (pin "17") (pinfunction "PB2_17") (pintype "bidirectional"))
    )
    (net (code "56") (name "SPI1_CS") (class "Default")
      (node (ref "R5") (pin "1") (pinfunction "1_1") (pintype "passive"))
      (node (ref "U1") (pin "11") (pinfunction "PA4_11") (pintype "bidirectional"))
    )
    (net (code "57") (name "SPI1_MISO") (class "Default")
      (node (ref "R3") (pin "1") (pinfunction "1_1") (pintype "passive"))
      (node (ref "U1") (pin "13") (pinfunction "PA6_13") (pintype "bidirectional"))
    )
    (net (code "58") (name "SPI1_MOSI") (class "Default")
      (node (ref "R1") (pin "1") (pinfunction "1_1") (pintype "passive"))
      (node (ref "U1") (pin "14") (pinfunction "PA7_14") (pintype "bidirectional"))
    )
    (net (code "59") (name "SPI1_SCK") (class "Default")
      (node (ref "R4") (pin "1") (pinfunction "1_1") (pintype "passive"))
      (node (ref "U1") (pin "12") (pinfunction "PA5_12") (pintype "bidirectional"))
    )
    (net (code "60") (name "SWCLK") (class "Default")
      (node (ref "SWCLK") (pin "PP") (pinfunction "TP_PP") (pintype "input"))
      (node (ref "U1") (pin "28") (pinfunction "PA14_28") (pintype "bidirectional"))
    )
    (net (code "61") (name "SWDIO") (class "Default")
      (node (ref "SWDIO") (pin "PP") (pinfunction "TP_PP") (pintype "input"))
      (node (ref "U1") (pin "25") (pinfunction "PA13_25") (pintype "bidirectional"))
    )
    (net (code "62") (name "USART1_RX") (class "Default")
      (node (ref "R9") (pin "2") (pinfunction "2_2") (pintype "passive"))
      (node (ref "U1") (pin "22") (pinfunction "PA10_22") (pintype "bidirectional"))
    )
    (net (code "63") (name "USART1_TX") (class "Default")
      (node (ref "R10") (pin "2") (pinfunction "2_2") (pintype "passive"))
      (node (ref "U1") (pin "21") (pinfunction "PA9_21") (pintype "bidirectional"))
    )
    (net (code "64") (name "USART2_RX") (class "Default")
      (node (ref "R22") (pin "1") (pinfunction "1_1") (pintype "passive"))
      (node (ref "U1") (pin "10") (pinfunction "PA3_10") (pintype "bidirectional"))
    )
    (net (code "65") (name "USART2_TX") (class "Default")
      (node (ref "R23") (pin "1") (pinfunction "1_1") (pintype "passive"))
      (node (ref "U1") (pin "9") (pinfunction "PA2_9") (pintype "bidirectional"))
    )
    (net (code "66") (name "VBUS") (class "Default")
      (node (ref "C16") (pin "1") (pinfunction "1_1") (pintype "passive"))
      (node (ref "C6") (pin "2") (pinfunction "2_2") (pintype "passive"))
      (node (ref "LED5") (pin "A") (pinfunction "A_A") (pintype "passive"))
      (node (ref "U$2") (pin "4") (pinfunction "VIN_4") (pintype "power_in"))
      (node (ref "U$4") (pin "10") (pinfunction "VCC_10") (pintype "power_in"))
      (node (ref "X2") (pin "VBUS") (pinfunction "VBUS_VBUS") (pintype "bidirectional"))
    )
    (net (code "67") (name "VCCIO") (class "Default")
      (node (ref "C19") (pin "1") (pinfunction "1_1") (pintype "passive"))
      (node (ref "LED1") (pin "A") (pinfunction "A_A") (pintype "passive"))
      (node (ref "LED2") (pin "A") (pinfunction "A_A") (pintype "passive"))
      (node (ref "U$4") (pin "1") (pinfunction "VCCIO_1") (pintype "input"))
      (node (ref "U$4") (pin "8") (pinfunction "3V3OUT_8") (pintype "output"))
      (node (ref "U$4") (pin "9") (pinfunction "RESET#_9") (pintype "input"))
    )
    (net (code "68") (name "VOLTAGE") (class "Default")
      (node (ref "C20") (pin "1") (pinfunction "1_1") (pintype "passive"))
      (node (ref "R12") (pin "1") (pinfunction "1_1") (pintype "passive"))
      (node (ref "R21") (pin "2") (pinfunction "2_2") (pintype "passive"))
      (node (ref "U1") (pin "7") (pinfunction "PA0_7") (pintype "bidirectional"))
    )
    (net (code "69") (name "unconnected-(IC1-PGOOD-Pad1)") (class "Default")
      (node (ref "IC1") (pin "1") (pinfunction "PGOOD_1") (pintype "output"))
    )
    (net (code "70") (name "unconnected-(U$3-AUX_CL-Pad7)") (class "Default")
      (node (ref "U$3") (pin "7") (pinfunction "AUX_CL_7") (pintype "output"))
    )
    (net (code "71") (name "unconnected-(U$3-AUX_DA-Pad6)") (class "Default")
      (node (ref "U$3") (pin "6") (pinfunction "AUX_DA_6") (pintype "bidirectional"))
    )
    (net (code "72") (name "unconnected-(U$3-CLKOUT-Pad22)") (class "Default")
      (node (ref "U$3") (pin "22") (pinfunction "CLKOUT_22") (pintype "output"))
    )
    (net (code "73") (name "unconnected-(U$3-INT-Pad12)") (class "Default")
      (node (ref "U$3") (pin "12") (pinfunction "INT_12") (pintype "output"))
    )
    (net (code "74") (name "unconnected-(U$3-NC1-Pad2)") (class "Default")
      (node (ref "U$3") (pin "2") (pinfunction "NC1_2") (pintype "no_connect"))
    )
    (net (code "75") (name "unconnected-(U$3-NC2-Pad3)") (class "Default")
      (node (ref "U$3") (pin "3") (pinfunction "NC2_3") (pintype "no_connect"))
    )
    (net (code "76") (name "unconnected-(U$3-NC3-Pad4)") (class "Default")
      (node (ref "U$3") (pin "4") (pinfunction "NC3_4") (pintype "no_connect"))
    )
    (net (code "77") (name "unconnected-(U$3-NC4-Pad5)") (class "Default")
      (node (ref "U$3") (pin "5") (pinfunction "NC4_5") (pintype "no_connect"))
    )
    (net (code "78") (name "unconnected-(U$3-NC5-Pad14)") (class "Default")
      (node (ref "U$3") (pin "14") (pinfunction "NC5_14") (pintype "no_connect"))
    )
    (net (code "79") (name "unconnected-(U$3-NC6-Pad15)") (class "Default")
      (node (ref "U$3") (pin "15") (pinfunction "NC6_15") (pintype "no_connect"))
    )
    (net (code "80") (name "unconnected-(U$3-NC7-Pad16)") (class "Default")
      (node (ref "U$3") (pin "16") (pinfunction "NC7_16") (pintype "no_connect"))
    )
    (net (code "81") (name "unconnected-(U$3-NC8-Pad17)") (class "Default")
      (node (ref "U$3") (pin "17") (pinfunction "NC8_17") (pintype "no_connect"))
    )
    (net (code "82") (name "unconnected-(U$3-RESV1-Pad19)") (class "Default")
      (node (ref "U$3") (pin "19") (pinfunction "RESV1_19") (pintype "no_connect"))
    )
    (net (code "83") (name "unconnected-(U$3-RESV2-Pad21)") (class "Default")
      (node (ref "U$3") (pin "21") (pinfunction "RESV2_21") (pintype "no_connect"))
    )
    (net (code "84") (name "unconnected-(U$3-TP-Pad25)") (class "Default")
      (node (ref "U$3") (pin "25") (pinfunction "TP_25") (pintype "bidirectional"))
    )
    (net (code "85") (name "unconnected-(U$4-CBUS0-Pad12)") (class "Default")
      (node (ref "U$4") (pin "12") (pinfunction "CBUS0_12") (pintype "bidirectional"))
    )
    (net (code "86") (name "unconnected-(U$4-CBUS3-Pad14)") (class "Default")
      (node (ref "U$4") (pin "14") (pinfunction "CBUS3_14") (pintype "bidirectional"))
    )
    (net (code "87") (name "unconnected-(U$4-CTS#-Pad4)") (class "Default")
      (node (ref "U$4") (pin "4") (pinfunction "CTS#_4") (pintype "bidirectional"))
    )
    (net (code "88") (name "unconnected-(U$4-RTS#-Pad16)") (class "Default")
      (node (ref "U$4") (pin "16") (pinfunction "RTS#_16") (pintype "bidirectional"))
    )
    (net (code "89") (name "unconnected-(U1B-PA8-Pad20)") (class "Default")
      (node (ref "U1") (pin "20") (pinfunction "PA8_20") (pintype "bidirectional"))
    )
    (net (code "90") (name "unconnected-(U1B-PA11-Pad23)") (class "Default")
      (node (ref "U1") (pin "23") (pinfunction "PA11_23") (pintype "bidirectional"))
    )
    (net (code "91") (name "unconnected-(U1B-PA12-Pad24)") (class "Default")
      (node (ref "U1") (pin "24") (pinfunction "PA12_24") (pintype "bidirectional"))
    )
    (net (code "92") (name "unconnected-(U1D-PB6-Pad33)") (class "Default")
      (node (ref "U1") (pin "33") (pinfunction "PB6_33") (pintype "bidirectional"))
    )
    (net (code "93") (name "unconnected-(U1D-PB7-Pad34)") (class "Default")
      (node (ref "U1") (pin "34") (pinfunction "PB7_34") (pintype "bidirectional"))
    )
    (net (code "94") (name "unconnected-(X2-PadID)") (class "Default")
      (node (ref "X2") (pin "ID") (pinfunction "ID_ID") (pintype "bidirectional"))
    )
  )
)
